# 12_40PIN_FAN.net
KiCad netlist of a schematic drawn in Altium Designer
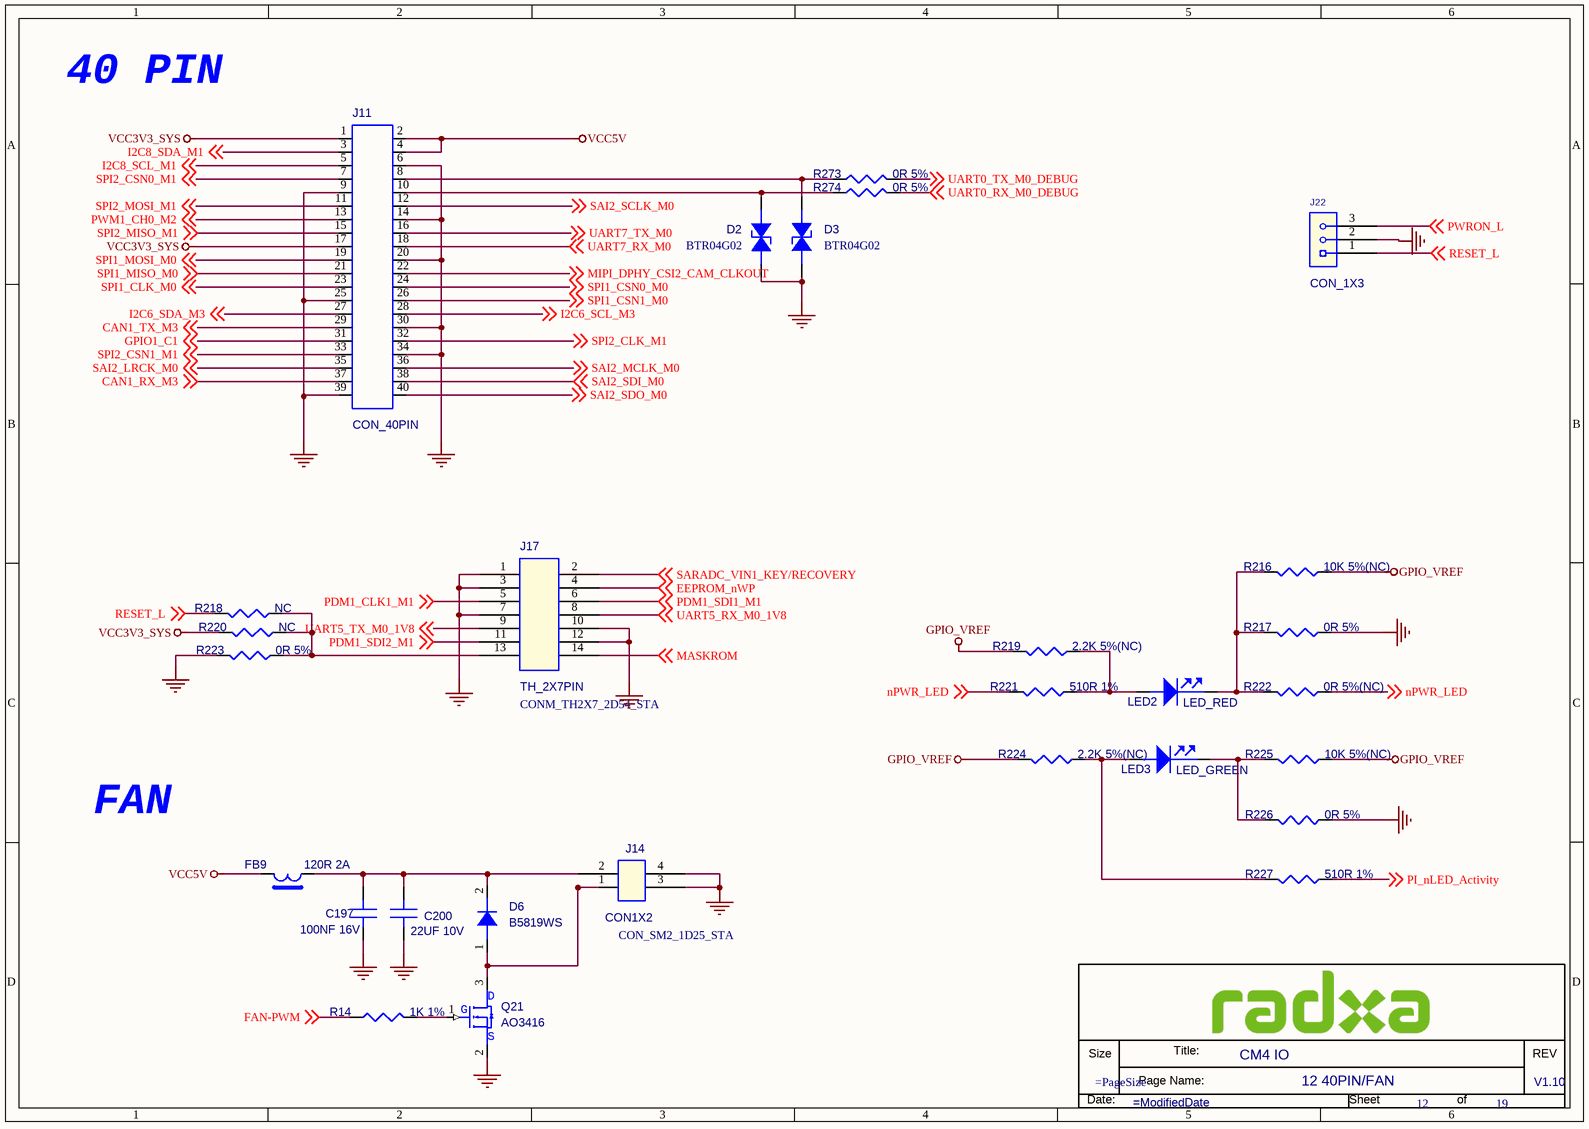
[diagram p0: 12 40PIN_FAN.SchDoc]

(export (version "E")
  (design (tool "Eeschema 10.0.6"))
  (components
    (comp (ref "C197")
      (value "100NF 16V")
      (footprint "C0201")
      (description "SMD  0201  100NF  16V  X5R  ±20%  ROHS")
      (fields (field (name "PART NUMBER") "A1C01.00099"))
      (libsource (lib "*") (part "C"))
    )
    (comp (ref "C200")
      (value "22UF 10V")
      (footprint "C0603")
      (description "SMD  0603  22UF  10V  X5R  ±20%  ROHS")
      (fields (field (name "PART NUMBER") "A1C01.00015"))
      (libsource (lib "*") (part "C"))
    )
    (comp (ref "D2")
      (value "BTR04G02")
      (footprint "DFN1006-2L")
      (description "SMD  编带  0402  BTR04G02  B-tron  ROHS")
      (fields (field (name "PART NUMBER") "A1D02.00002"))
      (libsource (lib "*") (part "ESD"))
    )
    (comp (ref "D3")
      (value "BTR04G02")
      (footprint "DFN1006-2L")
      (description "SMD  编带  0402  BTR04G02  B-tron  ROHS")
      (fields (field (name "PART NUMBER") "A1D02.00002"))
      (libsource (lib "*") (part "ESD"))
    )
    (comp (ref "D6")
      (value "B5819WS")
      (footprint "SOD_323")
      (description "SMD  编带  SOD-323  B5819WS  CJ  ROHS")
      (fields
        (field (name "MANUFACTURER") "长电")
        (field (name "PART NUMBER") "A1D02.00005")
        (field (name "CREATED BY") "JJJ")
      )
      (libsource (lib "*") (part "DIODE_Dup1"))
    )
    (comp (ref "FB9")
      (value "120R 2A")
      (footprint "FB0402")
      (description "SMD  0402  FB120R  2A  ±25%  ROHS")
      (fields (field (name "PART NUMBER") "A1L09.00004"))
      (libsource (lib "*") (part "BEAD"))
    )
    (comp (ref "J11")
      (value "CON_40PIN")
      (footprint "CON_TH20X2_2D54_STA")
      (fields (field (name "PART NUMBER") "A1J01.00012"))
      (libsource (lib "*") (part "CON_TH2X20"))
    )
    (comp (ref "J14")
      (value "CON1X2")
      (footprint "CON_SM2_1D25_STA")
      (description "SMD  母座  1*2PIN  90度  立贴  1.25mm脚距  9T  X9821WVS-02-9TSN  白色  星坤  ROHS")
      (fields (field (name "PART NUMBER") "A1J01.00089") (field (name "PCB FOOTPRINT") "CON_SM2_1D25_STA"))
      (libsource (lib "*") (part "CON_1X2"))
    )
    (comp (ref "J17")
      (value "TH_2X7PIN")
      (footprint "CONM_TH2X7_2D54_STA")
      (fields (field (name "PART NUMBER") "A1J02.00017") (field (name "PCB FOOTPRINT") "CONM_TH2X7_2D54_STA"))
      (libsource (lib "*") (part "TH_2X7PIN"))
    )
    (comp (ref "J22")
      (value "CON_1X3")
      (footprint "CON_TH1X3_2D54_STA")
      (fields (field (name "PART NUMBER") "A1J02.00013"))
      (libsource (lib "*") (part "CON_1X3"))
    )
    (comp (ref "LED2")
      (value "LED_RED")
      (footprint "LED_D0603")
      (description "SMD  编带  0603  发红光  单色  mcd=150  IF=20mA  无色散光  EY-PB0603RC-010F  恩域光电  ROHS")
      (fields (field (name "PART NUMBER") "A1D03.00003") (field (name "CREATED BY") "JJJ"))
      (libsource (lib "*") (part "LED"))
    )
    (comp (ref "LED3")
      (value "LED_GREEN")
      (footprint "LED_D0603")
      (description "SMD  编带  0603  发绿光  单色  mcd=150  IF=20mA  无色散光  EY-TB0603GC-010F  恩域光电  ROHS")
      (fields (field (name "PART NUMBER") "A1D03.00002") (field (name "CREATED BY") "JJJ"))
      (libsource (lib "*") (part "LED"))
    )
    (comp (ref "Q21")
      (value "AO3416")
      (footprint "SOT_23")
      (description "SMD  编带  SOT-23-3L  AO3416  N沟道  AOS  ROHS")
      (fields (field (name "PART NUMBER") "A1D01.00010"))
      (libsource (lib "*") (part "MOSFET_NPN"))
    )
    (comp (ref "R14")
      (value "1K 1%")
      (footprint "R0402")
      (description "SMD  0201  1K  1/20W  ±1%  ROHS")
      (fields (field (name "PART NUMBER") "A1R01.00111"))
      (libsource (lib "*") (part "R"))
    )
    (comp (ref "R216")
      (value "10K 5%(NC)")
      (footprint "R0402")
      (description "SMD  0201  10K  1/20W  ±5%  ROHS")
      (fields (field (name "PART NUMBER") "A1R01.00012"))
      (libsource (lib "*") (part "R"))
    )
    (comp (ref "R217")
      (value "0R 5%")
      (footprint "R0402")
      (description "SMD  0201  0R  1/20W  ±5%  ROHS")
      (fields (field (name "PART NUMBER") "A1R01.00027"))
      (libsource (lib "*") (part "R"))
    )
    (comp (ref "R218")
      (value "NC")
      (footprint "R0402")
      (description "SMD  0201  0R  1/20W  ±5%  ROHS")
      (fields (field (name "PART NUMBER") "A1R01.00027"))
      (libsource (lib "*") (part "R"))
    )
    (comp (ref "R219")
      (value "2.2K 5%(NC)")
      (footprint "R0402")
      (description "SMD  0201  2.2K  1/20W  ±5%  ROHS")
      (fields (field (name "PART NUMBER") "A1R01.00016"))
      (libsource (lib "*") (part "R"))
    )
    (comp (ref "R220")
      (value "NC")
      (footprint "R0402")
      (description "SMD  0201  10K  1/20W  ±5%  ROHS")
      (fields (field (name "PART NUMBER") "A1R01.00012"))
      (libsource (lib "*") (part "R"))
    )
    (comp (ref "R221")
      (value "510R 1%")
      (footprint "R0402")
      (description "SMD  0201  2.2K  1/20W  ±5%  ROHS")
      (fields (field (name "PART NUMBER") "A1R01.00016"))
      (libsource (lib "*") (part "R"))
    )
    (comp (ref "R222")
      (value "0R 5%(NC)")
      (footprint "R0402")
      (description "SMD  0201  0R  1/20W  ±5%  ROHS")
      (fields (field (name "PART NUMBER") "A1R01.00027"))
      (libsource (lib "*") (part "R"))
    )
    (comp (ref "R223")
      (value "0R 5%")
      (footprint "R0402")
      (description "SMD  0201  0R  1/20W  ±5%  ROHS")
      (fields (field (name "PART NUMBER") "A1R01.00027"))
      (libsource (lib "*") (part "R"))
    )
    (comp (ref "R224")
      (value "2.2K 5%(NC)")
      (footprint "R0402")
      (description "SMD  0201  2.2K  1/20W  ±5%  ROHS")
      (fields (field (name "PART NUMBER") "A1R01.00016"))
      (libsource (lib "*") (part "R"))
    )
    (comp (ref "R225")
      (value "10K 5%(NC)")
      (footprint "R0402")
      (description "SMD  0201  10K  1/20W  ±5%  ROHS")
      (fields (field (name "PART NUMBER") "A1R01.00012"))
      (libsource (lib "*") (part "R"))
    )
    (comp (ref "R226")
      (value "0R 5%")
      (footprint "R0402")
      (description "SMD  0201  0R  1/20W  ±5%  ROHS")
      (fields (field (name "PART NUMBER") "A1R01.00027"))
      (libsource (lib "*") (part "R"))
    )
    (comp (ref "R227")
      (value "510R 1%")
      (footprint "R0402")
      (description "SMD  0201  0R  1/20W  ±5%  ROHS")
      (fields (field (name "PART NUMBER") "A1R01.00027"))
      (libsource (lib "*") (part "R"))
    )
    (comp (ref "R273")
      (value "0R 5%")
      (footprint "R0402")
      (description "SMD  0201  0R  1/20W  ±5%  ROHS")
      (fields (field (name "PART NUMBER") "A1R01.00027"))
      (libsource (lib "*") (part "R"))
    )
    (comp (ref "R274")
      (value "0R 5%")
      (footprint "R0402")
      (description "SMD  0201  0R  1/20W  ±5%  ROHS")
      (fields (field (name "PART NUMBER") "A1R01.00027"))
      (libsource (lib "*") (part "R"))
    )
  )
  (nets
    (net (code "1") (name "CAN1_RX_M3") (class "Default")
      (node (ref "J11") (pin "37") (pinfunction "37_37") (pintype "bidirectional"))
    )
    (net (code "2") (name "CAN1_TX_M3") (class "Default")
      (node (ref "J11") (pin "29") (pinfunction "29_29") (pintype "bidirectional"))
    )
    (net (code "3") (name "EEPROM_nWP") (class "Default")
      (node (ref "J17") (pin "4") (pinfunction "4_4") (pintype "passive"))
    )
    (net (code "4") (name "FAN-PWM") (class "Default")
      (node (ref "R14") (pin "1") (pinfunction "1_1") (pintype "passive"))
    )
    (net (code "5") (name "GND") (class "Default")
      (node (ref "C197") (pin "2") (pinfunction "B_2") (pintype "passive"))
      (node (ref "C200") (pin "2") (pinfunction "B_2") (pintype "passive"))
      (node (ref "D2") (pin "2") (pinfunction "CATHODE_2") (pintype "passive"))
      (node (ref "D3") (pin "2") (pinfunction "CATHODE_2") (pintype "passive"))
      (node (ref "J11") (pin "14") (pinfunction "14_14") (pintype "bidirectional"))
      (node (ref "J11") (pin "20") (pinfunction "20_20") (pintype "bidirectional"))
      (node (ref "J11") (pin "25") (pinfunction "25_25") (pintype "bidirectional"))
      (node (ref "J11") (pin "30") (pinfunction "30_30") (pintype "bidirectional"))
      (node (ref "J11") (pin "34") (pinfunction "34_34") (pintype "bidirectional"))
      (node (ref "J11") (pin "39") (pinfunction "39_39") (pintype "bidirectional"))
      (node (ref "J11") (pin "6") (pinfunction "6_6") (pintype "bidirectional"))
      (node (ref "J11") (pin "9") (pinfunction "9_9") (pintype "bidirectional"))
      (node (ref "J14") (pin "3") (pinfunction "3_3") (pintype "passive"))
      (node (ref "J14") (pin "4") (pinfunction "4_4") (pintype "passive"))
      (node (ref "J17") (pin "1") (pinfunction "1_1") (pintype "passive"))
      (node (ref "J17") (pin "10") (pinfunction "10_10") (pintype "passive"))
      (node (ref "J17") (pin "12") (pinfunction "12_12") (pintype "passive"))
      (node (ref "J17") (pin "3") (pinfunction "3_3") (pintype "passive"))
      (node (ref "J17") (pin "7") (pinfunction "7_7") (pintype "passive"))
      (node (ref "J22") (pin "2") (pinfunction "2_2") (pintype "passive"))
      (node (ref "Q21") (pin "2") (pinfunction "S_2") (pintype "passive"))
      (node (ref "R217") (pin "2") (pinfunction "2_2") (pintype "passive"))
      (node (ref "R223") (pin "2") (pinfunction "2_2") (pintype "passive"))
      (node (ref "R226") (pin "2") (pinfunction "2_2") (pintype "passive"))
    )
    (net (code "6") (name "GPIO1_C1") (class "Default")
      (node (ref "J11") (pin "31") (pinfunction "31_31") (pintype "bidirectional"))
    )
    (net (code "7") (name "GPIO_VREF") (class "Default")
      (node (ref "R216") (pin "2") (pinfunction "2_2") (pintype "passive"))
      (node (ref "R219") (pin "1") (pinfunction "1_1") (pintype "passive"))
      (node (ref "R224") (pin "1") (pinfunction "1_1") (pintype "passive"))
      (node (ref "R225") (pin "2") (pinfunction "2_2") (pintype "passive"))
    )
    (net (code "8") (name "I2C6_SCL_M3") (class "Default")
      (node (ref "J11") (pin "28") (pinfunction "28_28") (pintype "bidirectional"))
    )
    (net (code "9") (name "I2C6_SDA_M3") (class "Default")
      (node (ref "J11") (pin "27") (pinfunction "27_27") (pintype "bidirectional"))
    )
    (net (code "10") (name "I2C8_SCL_M1") (class "Default")
      (node (ref "J11") (pin "5") (pinfunction "5_5") (pintype "bidirectional"))
    )
    (net (code "11") (name "I2C8_SDA_M1") (class "Default")
      (node (ref "J11") (pin "3") (pinfunction "3_3") (pintype "bidirectional"))
    )
    (net (code "12") (name "MASKROM") (class "Default")
      (node (ref "J17") (pin "14") (pinfunction "14_14") (pintype "passive"))
    )
    (net (code "13") (name "MIPI_DPHY_CSI2_CAM_CLKOUT") (class "Default")
      (node (ref "J11") (pin "22") (pinfunction "22_22") (pintype "bidirectional"))
    )
    (net (code "14") (name "Net-(C197-A)") (class "Default")
      (node (ref "C197") (pin "1") (pinfunction "A_1") (pintype "passive"))
      (node (ref "C200") (pin "1") (pinfunction "A_1") (pintype "passive"))
      (node (ref "D6") (pin "2") (pinfunction "K_2") (pintype "passive"))
      (node (ref "FB9") (pin "2") (pinfunction "2_2") (pintype "passive"))
      (node (ref "J14") (pin "2") (pinfunction "2_2") (pintype "passive"))
    )
    (net (code "15") (name "Net-(D2-ANODE)") (class "Default")
      (node (ref "D2") (pin "1") (pinfunction "ANODE_1") (pintype "passive"))
      (node (ref "J11") (pin "10") (pinfunction "10_10") (pintype "bidirectional"))
      (node (ref "R274") (pin "1") (pinfunction "1_1") (pintype "passive"))
    )
    (net (code "16") (name "Net-(D3-ANODE)") (class "Default")
      (node (ref "D3") (pin "1") (pinfunction "ANODE_1") (pintype "passive"))
      (node (ref "J11") (pin "8") (pinfunction "8_8") (pintype "bidirectional"))
      (node (ref "R273") (pin "1") (pinfunction "1_1") (pintype "passive"))
    )
    (net (code "17") (name "Net-(D6-A)") (class "Default")
      (node (ref "D6") (pin "1") (pinfunction "A_1") (pintype "passive"))
      (node (ref "J14") (pin "1") (pinfunction "1_1") (pintype "passive"))
      (node (ref "Q21") (pin "3") (pinfunction "D_3") (pintype "passive"))
    )
    (net (code "18") (name "Net-(J17-Pad13)") (class "Default")
      (node (ref "J17") (pin "13") (pinfunction "13_13") (pintype "passive"))
      (node (ref "R218") (pin "1") (pinfunction "1_1") (pintype "passive"))
      (node (ref "R220") (pin "1") (pinfunction "1_1") (pintype "passive"))
      (node (ref "R223") (pin "1") (pinfunction "1_1") (pintype "passive"))
    )
    (net (code "19") (name "Net-(LED2-ANODE)") (class "Default")
      (node (ref "LED2") (pin "1") (pinfunction "ANODE_1") (pintype "passive"))
      (node (ref "R219") (pin "2") (pinfunction "2_2") (pintype "passive"))
      (node (ref "R221") (pin "2") (pinfunction "2_2") (pintype "passive"))
    )
    (net (code "20") (name "Net-(LED2-CATHODE)") (class "Default")
      (node (ref "LED2") (pin "2") (pinfunction "CATHODE_2") (pintype "passive"))
      (node (ref "R216") (pin "1") (pinfunction "1_1") (pintype "passive"))
      (node (ref "R217") (pin "1") (pinfunction "1_1") (pintype "passive"))
      (node (ref "R222") (pin "1") (pinfunction "1_1") (pintype "passive"))
    )
    (net (code "21") (name "Net-(LED3-ANODE)") (class "Default")
      (node (ref "LED3") (pin "1") (pinfunction "ANODE_1") (pintype "passive"))
      (node (ref "R224") (pin "2") (pinfunction "2_2") (pintype "passive"))
      (node (ref "R227") (pin "1") (pinfunction "1_1") (pintype "passive"))
    )
    (net (code "22") (name "Net-(LED3-CATHODE)") (class "Default")
      (node (ref "LED3") (pin "2") (pinfunction "CATHODE_2") (pintype "passive"))
      (node (ref "R225") (pin "1") (pinfunction "1_1") (pintype "passive"))
      (node (ref "R226") (pin "1") (pinfunction "1_1") (pintype "passive"))
    )
    (net (code "23") (name "Net-(Q21-G)") (class "Default")
      (node (ref "Q21") (pin "1") (pinfunction "G_1") (pintype "input"))
      (node (ref "R14") (pin "2") (pinfunction "2_2") (pintype "passive"))
    )
    (net (code "24") (name "PDM1_CLK1_M1") (class "Default")
      (node (ref "J17") (pin "5") (pinfunction "5_5") (pintype "passive"))
    )
    (net (code "25") (name "PDM1_SDI1_M1") (class "Default")
      (node (ref "J17") (pin "6") (pinfunction "6_6") (pintype "passive"))
    )
    (net (code "26") (name "PDM1_SDI2_M1") (class "Default")
      (node (ref "J17") (pin "11") (pinfunction "11_11") (pintype "passive"))
    )
    (net (code "27") (name "PI_nLED_Activity") (class "Default")
      (node (ref "R227") (pin "2") (pinfunction "2_2") (pintype "passive"))
    )
    (net (code "28") (name "PWM1_CH0_M2") (class "Default")
      (node (ref "J11") (pin "13") (pinfunction "13_13") (pintype "bidirectional"))
    )
    (net (code "29") (name "PWRON_L") (class "Default")
      (node (ref "J22") (pin "3") (pinfunction "3_3") (pintype "passive"))
    )
    (net (code "30") (name "RESET_L") (class "Default")
      (node (ref "J22") (pin "1") (pinfunction "1_1") (pintype "passive"))
      (node (ref "R218") (pin "2") (pinfunction "2_2") (pintype "passive"))
    )
    (net (code "31") (name "SAI2_LRCK_M0") (class "Default")
      (node (ref "J11") (pin "35") (pinfunction "35_35") (pintype "bidirectional"))
    )
    (net (code "32") (name "SAI2_MCLK_M0") (class "Default")
      (node (ref "J11") (pin "36") (pinfunction "36_36") (pintype "bidirectional"))
    )
    (net (code "33") (name "SAI2_SCLK_M0") (class "Default")
      (node (ref "J11") (pin "12") (pinfunction "12_12") (pintype "bidirectional"))
    )
    (net (code "34") (name "SAI2_SDI_M0") (class "Default")
      (node (ref "J11") (pin "38") (pinfunction "38_38") (pintype "bidirectional"))
    )
    (net (code "35") (name "SAI2_SDO_M0") (class "Default")
      (node (ref "J11") (pin "40") (pinfunction "40_40") (pintype "bidirectional"))
    )
    (net (code "36") (name "SARADC_VIN1_KEY{slash}RECOVERY") (class "Default")
      (node (ref "J17") (pin "2") (pinfunction "2_2") (pintype "passive"))
    )
    (net (code "37") (name "SPI1_CLK_M0") (class "Default")
      (node (ref "J11") (pin "23") (pinfunction "23_23") (pintype "bidirectional"))
    )
    (net (code "38") (name "SPI1_CSN0_M0") (class "Default")
      (node (ref "J11") (pin "24") (pinfunction "24_24") (pintype "bidirectional"))
    )
    (net (code "39") (name "SPI1_CSN1_M0") (class "Default")
      (node (ref "J11") (pin "26") (pinfunction "26_26") (pintype "bidirectional"))
    )
    (net (code "40") (name "SPI1_MISO_M0") (class "Default")
      (node (ref "J11") (pin "21") (pinfunction "21_21") (pintype "bidirectional"))
    )
    (net (code "41") (name "SPI1_MOSI_M0") (class "Default")
      (node (ref "J11") (pin "19") (pinfunction "19_19") (pintype "bidirectional"))
    )
    (net (code "42") (name "SPI2_CLK_M1") (class "Default")
      (node (ref "J11") (pin "32") (pinfunction "32_32") (pintype "bidirectional"))
    )
    (net (code "43") (name "SPI2_CSN0_M1") (class "Default")
      (node (ref "J11") (pin "7") (pinfunction "7_7") (pintype "bidirectional"))
    )
    (net (code "44") (name "SPI2_CSN1_M1") (class "Default")
      (node (ref "J11") (pin "33") (pinfunction "33_33") (pintype "bidirectional"))
    )
    (net (code "45") (name "SPI2_MISO_M1") (class "Default")
      (node (ref "J11") (pin "15") (pinfunction "15_15") (pintype "bidirectional"))
    )
    (net (code "46") (name "SPI2_MOSI_M1") (class "Default")
      (node (ref "J11") (pin "11") (pinfunction "11_11") (pintype "bidirectional"))
    )
    (net (code "47") (name "UART0_RX_M0_DEBUG") (class "Default")
      (node (ref "R274") (pin "2") (pinfunction "2_2") (pintype "passive"))
    )
    (net (code "48") (name "UART0_TX_M0_DEBUG") (class "Default")
      (node (ref "R273") (pin "2") (pinfunction "2_2") (pintype "passive"))
    )
    (net (code "49") (name "UART5_RX_M0_1V8") (class "Default")
      (node (ref "J17") (pin "8") (pinfunction "8_8") (pintype "passive"))
    )
    (net (code "50") (name "UART5_TX_M0_1V8") (class "Default")
      (node (ref "J17") (pin "9") (pinfunction "9_9") (pintype "passive"))
    )
    (net (code "51") (name "UART7_RX_M0") (class "Default")
      (node (ref "J11") (pin "18") (pinfunction "18_18") (pintype "bidirectional"))
    )
    (net (code "52") (name "UART7_TX_M0") (class "Default")
      (node (ref "J11") (pin "16") (pinfunction "16_16") (pintype "bidirectional"))
    )
    (net (code "53") (name "VCC3V3_SYS") (class "Default")
      (node (ref "J11") (pin "1") (pinfunction "1_1") (pintype "bidirectional"))
      (node (ref "J11") (pin "17") (pinfunction "17_17") (pintype "bidirectional"))
      (node (ref "R220") (pin "2") (pinfunction "2_2") (pintype "passive"))
    )
    (net (code "54") (name "VCC5V") (class "Default")
      (node (ref "FB9") (pin "1") (pinfunction "1_1") (pintype "passive"))
      (node (ref "J11") (pin "2") (pinfunction "2_2") (pintype "bidirectional"))
      (node (ref "J11") (pin "4") (pinfunction "4_4") (pintype "bidirectional"))
    )
    (net (code "55") (name "nPWR_LED") (class "Default")
      (node (ref "R221") (pin "1") (pinfunction "1_1") (pintype "passive"))
      (node (ref "R222") (pin "2") (pinfunction "2_2") (pintype "passive"))
    )
  )
)
